# SparkFun_Pogo_Pi_AVR_Programmer_ADAPTER-.net
KiCad netlist of a schematic drawn in EAGLE
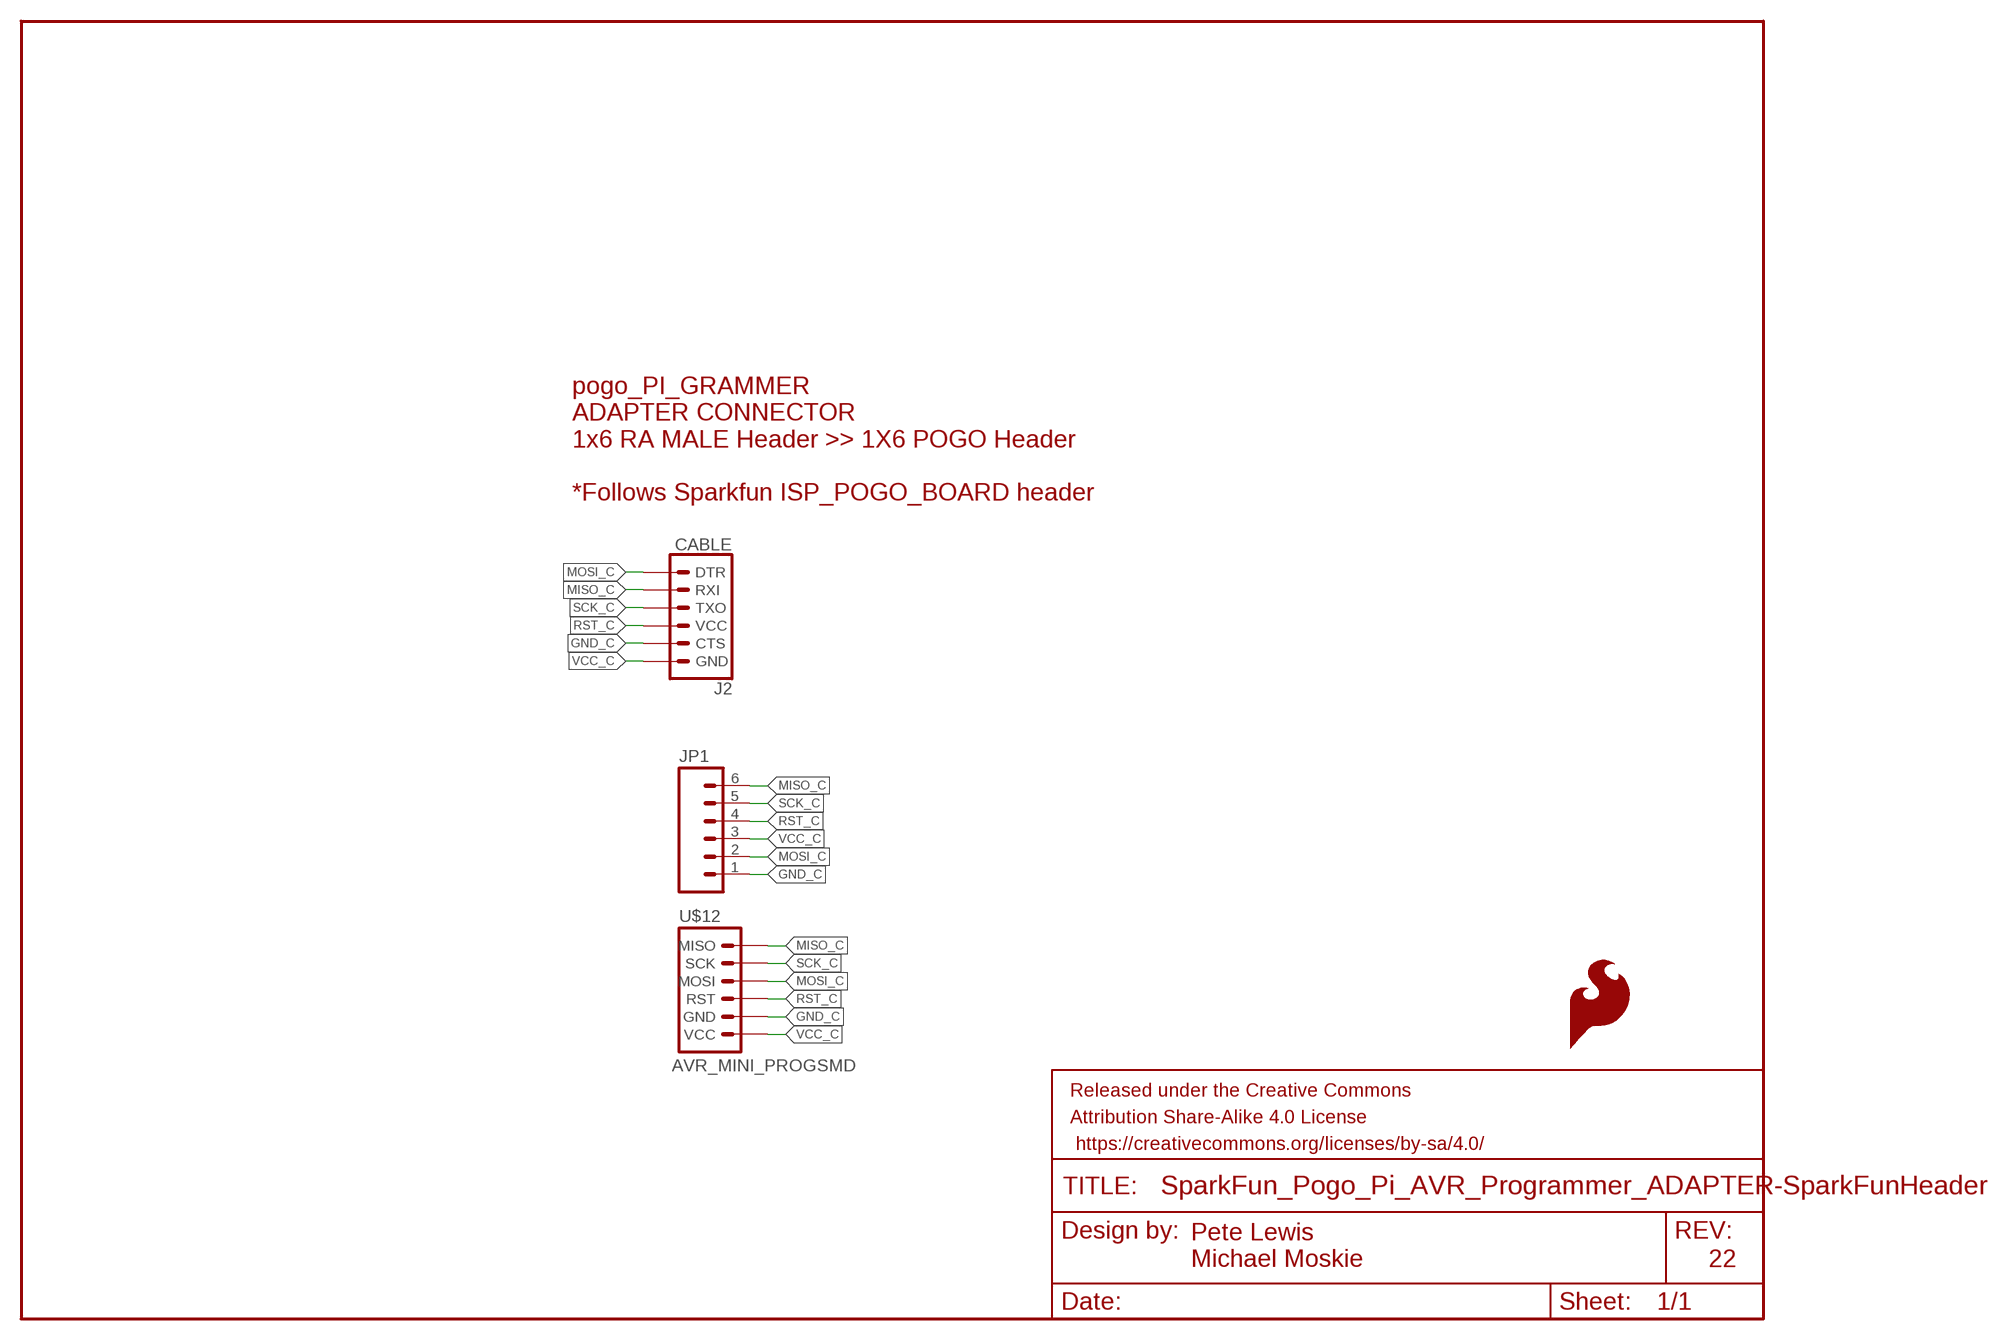
[diagram p0: schematic, sheet 1]

(export (version "E")
  (design (tool "Eeschema 10.0.6"))
  (components
    (comp (ref "FRAME1")
      (value "FRAME-LETTER")
      (footprint "eagle-import:CREATIVE_COMMONS")
      (libsource (lib "eagle-import") (part "FRAME-LETTER"))
    )
    (comp (ref "J2")
      (value "CABLE")
      (footprint "eagle-import:1X06-SMD_RA_MALE")
      (fields (field (name "PROD_ID") "CONN-10140"))
      (libsource (lib "eagle-import") (part "6_PIN_SERIAL_TARGETSMD"))
    )
    (comp (ref "JP1")
      (value "M06POLAR")
      (footprint "eagle-import:MOLEX-1X6")
      (libsource (lib "eagle-import") (part "M06POLAR"))
    )
    (comp (ref "LOGO1")
      (value "SFE_LOGO_FLAME.1_INCH")
      (footprint "eagle-import:SFE_LOGO_FLAME_.1")
      (libsource (lib "eagle-import") (part "SFE_LOGO_FLAME.1_INCH"))
    )
    (comp (ref "U$12")
      (value "AVR_MINI_PROGSMD")
      (footprint "eagle-import:AVR_MINI_PROG")
      (libsource (lib "eagle-import") (part "AVR_MINI_PROGSMD"))
    )
  )
  (nets
    (net (code "1") (name "GND_C") (class "Default")
      (node (ref "J2") (pin "5") (pinfunction "CTS_5") (pintype "passive"))
      (node (ref "JP1") (pin "1") (pinfunction "1_1") (pintype "passive"))
      (node (ref "U$12") (pin "2") (pinfunction "GND_2") (pintype "passive"))
    )
    (net (code "2") (name "MISO_C") (class "Default")
      (node (ref "J2") (pin "2") (pinfunction "RXI_2") (pintype "passive"))
      (node (ref "JP1") (pin "6") (pinfunction "6_6") (pintype "passive"))
      (node (ref "U$12") (pin "6") (pinfunction "MISO_6") (pintype "passive"))
    )
    (net (code "3") (name "MOSI_C") (class "Default")
      (node (ref "J2") (pin "1") (pinfunction "DTR_1") (pintype "passive"))
      (node (ref "JP1") (pin "2") (pinfunction "2_2") (pintype "passive"))
      (node (ref "U$12") (pin "4") (pinfunction "MOSI_4") (pintype "passive"))
    )
    (net (code "4") (name "RST_C") (class "Default")
      (node (ref "J2") (pin "4") (pinfunction "VCC_4") (pintype "passive"))
      (node (ref "JP1") (pin "4") (pinfunction "4_4") (pintype "passive"))
      (node (ref "U$12") (pin "3") (pinfunction "RST_3") (pintype "passive"))
    )
    (net (code "5") (name "SCK_C") (class "Default")
      (node (ref "J2") (pin "3") (pinfunction "TXO_3") (pintype "passive"))
      (node (ref "JP1") (pin "5") (pinfunction "5_5") (pintype "passive"))
      (node (ref "U$12") (pin "5") (pinfunction "SCK_5") (pintype "passive"))
    )
    (net (code "6") (name "VCC_C") (class "Default")
      (node (ref "J2") (pin "6") (pinfunction "GND_6") (pintype "passive"))
      (node (ref "JP1") (pin "3") (pinfunction "3_3") (pintype "passive"))
      (node (ref "U$12") (pin "1") (pinfunction "VCC_1") (pintype "passive"))
    )
  )
)
